# SubboardWithoutMotorsAndEM.net
KiCad netlist of a schematic drawn in EAGLE
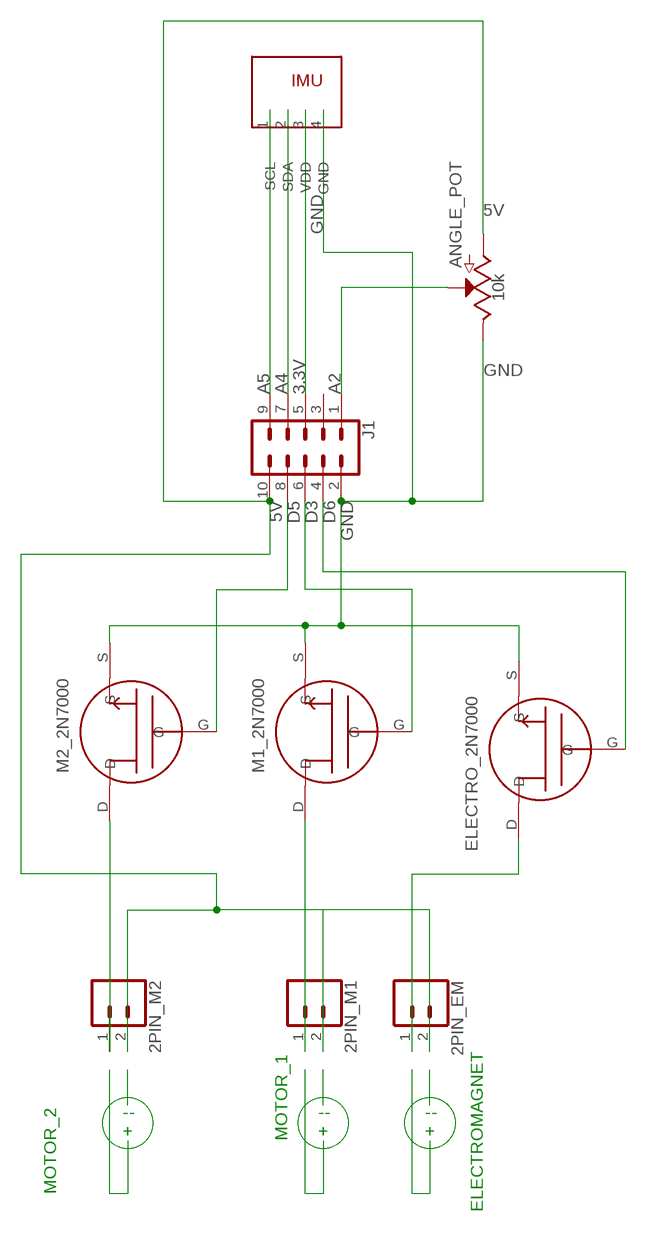
[diagram p0: schematic, sheet 1]

(export (version "E")
  (design (tool "Eeschema 10.0.6"))
  (components
    (comp (ref "2PIN_EM")
      (value "CONN_02")
      (footprint "eagle-import:1X02")
      (libsource (lib "eagle-import") (part "CONN_02"))
    )
    (comp (ref "2PIN_M1")
      (value "CONN_02")
      (footprint "eagle-import:1X02")
      (libsource (lib "eagle-import") (part "CONN_02"))
    )
    (comp (ref "2PIN_M2")
      (value "CONN_02")
      (footprint "eagle-import:1X02")
      (libsource (lib "eagle-import") (part "CONN_02"))
    )
    (comp (ref "ANGLE_POT")
      (value "10k")
      (footprint "eagle-import:POT-PTH-ALPS-KIT")
      (libsource (lib "eagle-import") (part "POTENTIOMETER-PTH-9MM-1/20W-20%-KIT"))
    )
    (comp (ref "ELECTRO_2N7000")
      (value "2N7000_N_FET")
      (footprint "eagle-import:2N7000_N_FET")
      (libsource (lib "eagle-import") (part "2N7000_N_FET"))
    )
    (comp (ref "J1")
      (value "CONN_05X2SHD")
      (footprint "eagle-import:2X5-SHROUDED")
      (libsource (lib "eagle-import") (part "CONN_05X2SHD"))
    )
    (comp (ref "M1_2N7000")
      (value "2N7000_N_FET")
      (footprint "eagle-import:2N7000_N_FET")
      (libsource (lib "eagle-import") (part "2N7000_N_FET"))
    )
    (comp (ref "M2_2N7000")
      (value "2N7000_N_FET")
      (footprint "eagle-import:2N7000_N_FET")
      (libsource (lib "eagle-import") (part "2N7000_N_FET"))
    )
    (comp (ref "U$1")
      (value "MPU-9250")
      (footprint "eagle-import:MPU-9250")
      (libsource (lib "eagle-import") (part "MPU-9250"))
    )
  )
  (nets
    (net (code "1") (name "/3.3V") (class "Default")
      (node (ref "J1") (pin "5") (pinfunction "5_5") (pintype "passive"))
      (node (ref "U$1") (pin "3") (pinfunction "VDD_3") (pintype "bidirectional"))
    )
    (net (code "2") (name "/5V") (class "Default")
      (node (ref "2PIN_EM") (pin "2") (pinfunction "2_2") (pintype "passive"))
      (node (ref "2PIN_M1") (pin "2") (pinfunction "2_2") (pintype "passive"))
      (node (ref "2PIN_M2") (pin "2") (pinfunction "2_2") (pintype "passive"))
      (node (ref "ANGLE_POT") (pin "P$3") (pinfunction "A_P$3") (pintype "passive"))
      (node (ref "J1") (pin "10") (pinfunction "10_10") (pintype "passive"))
    )
    (net (code "3") (name "/A2") (class "Default")
      (node (ref "ANGLE_POT") (pin "P$2") (pinfunction "S_P$2") (pintype "passive"))
      (node (ref "J1") (pin "1") (pinfunction "1_1") (pintype "passive"))
    )
    (net (code "4") (name "/A4") (class "Default")
      (node (ref "J1") (pin "7") (pinfunction "7_7") (pintype "passive"))
      (node (ref "U$1") (pin "2") (pinfunction "SDA_2") (pintype "bidirectional"))
    )
    (net (code "5") (name "/A5") (class "Default")
      (node (ref "J1") (pin "9") (pinfunction "9_9") (pintype "passive"))
      (node (ref "U$1") (pin "1") (pinfunction "SCL_1") (pintype "bidirectional"))
    )
    (net (code "6") (name "/D3") (class "Default")
      (node (ref "J1") (pin "6") (pinfunction "6_6") (pintype "passive"))
      (node (ref "M1_2N7000") (pin "G") (pinfunction "G_G") (pintype "bidirectional"))
    )
    (net (code "7") (name "/D5") (class "Default")
      (node (ref "J1") (pin "8") (pinfunction "8_8") (pintype "passive"))
      (node (ref "M2_2N7000") (pin "G") (pinfunction "G_G") (pintype "bidirectional"))
    )
    (net (code "8") (name "/D6") (class "Default")
      (node (ref "ELECTRO_2N7000") (pin "G") (pinfunction "G_G") (pintype "bidirectional"))
      (node (ref "J1") (pin "4") (pinfunction "4_4") (pintype "passive"))
    )
    (net (code "9") (name "/GND") (class "Default")
      (node (ref "ANGLE_POT") (pin "P$1") (pinfunction "E_P$1") (pintype "passive"))
      (node (ref "ELECTRO_2N7000") (pin "S") (pinfunction "S_S") (pintype "bidirectional"))
      (node (ref "J1") (pin "2") (pinfunction "2_2") (pintype "passive"))
      (node (ref "M1_2N7000") (pin "S") (pinfunction "S_S") (pintype "bidirectional"))
      (node (ref "M2_2N7000") (pin "S") (pinfunction "S_S") (pintype "bidirectional"))
      (node (ref "U$1") (pin "4") (pinfunction "GND_4") (pintype "bidirectional"))
    )
    (net (code "10") (name "Net-(2PIN_EM-Pad1)") (class "Default")
      (node (ref "2PIN_EM") (pin "1") (pinfunction "1_1") (pintype "passive"))
      (node (ref "ELECTRO_2N7000") (pin "D") (pinfunction "D_D") (pintype "bidirectional"))
    )
    (net (code "11") (name "Net-(2PIN_M1-Pad1)") (class "Default")
      (node (ref "2PIN_M1") (pin "1") (pinfunction "1_1") (pintype "passive"))
      (node (ref "M1_2N7000") (pin "D") (pinfunction "D_D") (pintype "bidirectional"))
    )
    (net (code "12") (name "Net-(2PIN_M2-Pad1)") (class "Default")
      (node (ref "2PIN_M2") (pin "1") (pinfunction "1_1") (pintype "passive"))
      (node (ref "M2_2N7000") (pin "D") (pinfunction "D_D") (pintype "bidirectional"))
    )
    (net (code "13") (name "unconnected-(J1-Pad3)") (class "Default")
      (node (ref "J1") (pin "3") (pinfunction "3_3") (pintype "passive"))
    )
  )
)
